# UV_exposure_led_v1_0.net
KiCad netlist of a schematic drawn in EAGLE
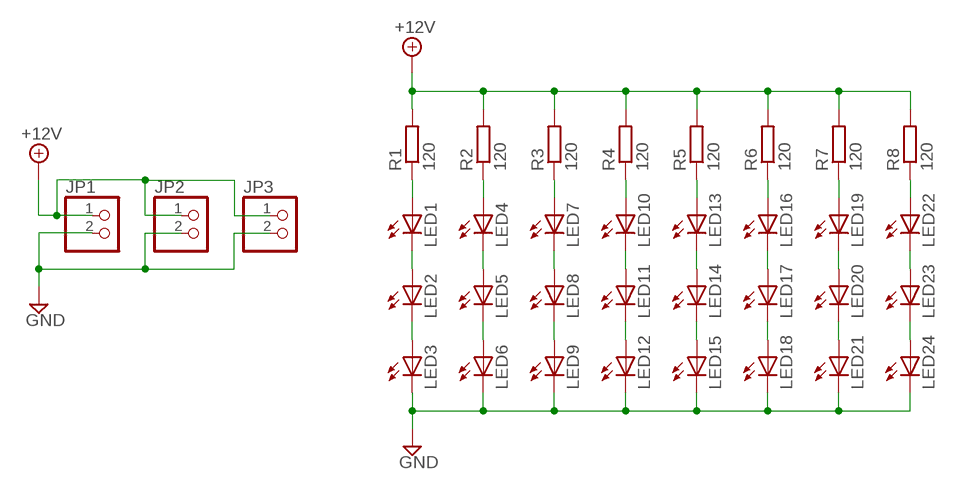
[diagram p0: schematic, sheet 1]

(export (version "E")
  (design (tool "Eeschema 10.0.6"))
  (components
    (comp (ref "JP1")
      (value "PINHD-1X2")
      (footprint "eagle-import:1X02")
      (libsource (lib "eagle-import") (part "PINHD-1X2"))
    )
    (comp (ref "JP2")
      (value "PINHD-1X2")
      (footprint "eagle-import:1X02")
      (libsource (lib "eagle-import") (part "PINHD-1X2"))
    )
    (comp (ref "JP3")
      (value "PINHD-1X2")
      (footprint "eagle-import:1X02")
      (libsource (lib "eagle-import") (part "PINHD-1X2"))
    )
    (comp (ref "LED1")
      (value "LED5MM")
      (footprint "eagle-import:LED5MM")
      (libsource (lib "eagle-import") (part "LED5MM"))
    )
    (comp (ref "LED2")
      (value "LED5MM")
      (footprint "eagle-import:LED5MM")
      (libsource (lib "eagle-import") (part "LED5MM"))
    )
    (comp (ref "LED3")
      (value "LED5MM")
      (footprint "eagle-import:LED5MM")
      (libsource (lib "eagle-import") (part "LED5MM"))
    )
    (comp (ref "LED4")
      (value "LED5MM")
      (footprint "eagle-import:LED5MM")
      (libsource (lib "eagle-import") (part "LED5MM"))
    )
    (comp (ref "LED5")
      (value "LED5MM")
      (footprint "eagle-import:LED5MM")
      (libsource (lib "eagle-import") (part "LED5MM"))
    )
    (comp (ref "LED6")
      (value "LED5MM")
      (footprint "eagle-import:LED5MM")
      (libsource (lib "eagle-import") (part "LED5MM"))
    )
    (comp (ref "LED7")
      (value "LED5MM")
      (footprint "eagle-import:LED5MM")
      (libsource (lib "eagle-import") (part "LED5MM"))
    )
    (comp (ref "LED8")
      (value "LED5MM")
      (footprint "eagle-import:LED5MM")
      (libsource (lib "eagle-import") (part "LED5MM"))
    )
    (comp (ref "LED9")
      (value "LED5MM")
      (footprint "eagle-import:LED5MM")
      (libsource (lib "eagle-import") (part "LED5MM"))
    )
    (comp (ref "LED10")
      (value "LED5MM")
      (footprint "eagle-import:LED5MM")
      (libsource (lib "eagle-import") (part "LED5MM"))
    )
    (comp (ref "LED11")
      (value "LED5MM")
      (footprint "eagle-import:LED5MM")
      (libsource (lib "eagle-import") (part "LED5MM"))
    )
    (comp (ref "LED12")
      (value "LED5MM")
      (footprint "eagle-import:LED5MM")
      (libsource (lib "eagle-import") (part "LED5MM"))
    )
    (comp (ref "LED13")
      (value "LED5MM")
      (footprint "eagle-import:LED5MM")
      (libsource (lib "eagle-import") (part "LED5MM"))
    )
    (comp (ref "LED14")
      (value "LED5MM")
      (footprint "eagle-import:LED5MM")
      (libsource (lib "eagle-import") (part "LED5MM"))
    )
    (comp (ref "LED15")
      (value "LED5MM")
      (footprint "eagle-import:LED5MM")
      (libsource (lib "eagle-import") (part "LED5MM"))
    )
    (comp (ref "LED16")
      (value "LED5MM")
      (footprint "eagle-import:LED5MM")
      (libsource (lib "eagle-import") (part "LED5MM"))
    )
    (comp (ref "LED17")
      (value "LED5MM")
      (footprint "eagle-import:LED5MM")
      (libsource (lib "eagle-import") (part "LED5MM"))
    )
    (comp (ref "LED18")
      (value "LED5MM")
      (footprint "eagle-import:LED5MM")
      (libsource (lib "eagle-import") (part "LED5MM"))
    )
    (comp (ref "LED19")
      (value "LED5MM")
      (footprint "eagle-import:LED5MM")
      (libsource (lib "eagle-import") (part "LED5MM"))
    )
    (comp (ref "LED20")
      (value "LED5MM")
      (footprint "eagle-import:LED5MM")
      (libsource (lib "eagle-import") (part "LED5MM"))
    )
    (comp (ref "LED21")
      (value "LED5MM")
      (footprint "eagle-import:LED5MM")
      (libsource (lib "eagle-import") (part "LED5MM"))
    )
    (comp (ref "LED22")
      (value "LED5MM")
      (footprint "eagle-import:LED5MM")
      (libsource (lib "eagle-import") (part "LED5MM"))
    )
    (comp (ref "LED23")
      (value "LED5MM")
      (footprint "eagle-import:LED5MM")
      (libsource (lib "eagle-import") (part "LED5MM"))
    )
    (comp (ref "LED24")
      (value "LED5MM")
      (footprint "eagle-import:LED5MM")
      (libsource (lib "eagle-import") (part "LED5MM"))
    )
    (comp (ref "R1")
      (value "120")
      (footprint "eagle-import:R1206W")
      (libsource (lib "eagle-import") (part "R-EU_R1206W"))
    )
    (comp (ref "R2")
      (value "120")
      (footprint "eagle-import:R1206W")
      (libsource (lib "eagle-import") (part "R-EU_R1206W"))
    )
    (comp (ref "R3")
      (value "120")
      (footprint "eagle-import:R1206W")
      (libsource (lib "eagle-import") (part "R-EU_R1206W"))
    )
    (comp (ref "R4")
      (value "120")
      (footprint "eagle-import:R1206W")
      (libsource (lib "eagle-import") (part "R-EU_R1206W"))
    )
    (comp (ref "R5")
      (value "120")
      (footprint "eagle-import:R1206W")
      (libsource (lib "eagle-import") (part "R-EU_R1206W"))
    )
    (comp (ref "R6")
      (value "120")
      (footprint "eagle-import:R1206W")
      (libsource (lib "eagle-import") (part "R-EU_R1206W"))
    )
    (comp (ref "R7")
      (value "120")
      (footprint "eagle-import:R1206W")
      (libsource (lib "eagle-import") (part "R-EU_R1206W"))
    )
    (comp (ref "R8")
      (value "120")
      (footprint "eagle-import:R1206W")
      (libsource (lib "eagle-import") (part "R-EU_R1206W"))
    )
  )
  (nets
    (net (code "1") (name "+12V") (class "Default")
      (node (ref "JP1") (pin "1") (pinfunction "1_1") (pintype "passive"))
      (node (ref "JP2") (pin "1") (pinfunction "1_1") (pintype "passive"))
      (node (ref "JP3") (pin "1") (pinfunction "1_1") (pintype "passive"))
      (node (ref "R1") (pin "2") (pinfunction "2_2") (pintype "passive"))
      (node (ref "R2") (pin "2") (pinfunction "2_2") (pintype "passive"))
      (node (ref "R3") (pin "2") (pinfunction "2_2") (pintype "passive"))
      (node (ref "R4") (pin "2") (pinfunction "2_2") (pintype "passive"))
      (node (ref "R5") (pin "2") (pinfunction "2_2") (pintype "passive"))
      (node (ref "R6") (pin "2") (pinfunction "2_2") (pintype "passive"))
      (node (ref "R7") (pin "2") (pinfunction "2_2") (pintype "passive"))
      (node (ref "R8") (pin "2") (pinfunction "2_2") (pintype "passive"))
    )
    (net (code "2") (name "GND") (class "Default")
      (node (ref "JP1") (pin "2") (pinfunction "2_2") (pintype "passive"))
      (node (ref "JP2") (pin "2") (pinfunction "2_2") (pintype "passive"))
      (node (ref "JP3") (pin "2") (pinfunction "2_2") (pintype "passive"))
      (node (ref "LED12") (pin "K") (pinfunction "C_K") (pintype "passive"))
      (node (ref "LED15") (pin "K") (pinfunction "C_K") (pintype "passive"))
      (node (ref "LED18") (pin "K") (pinfunction "C_K") (pintype "passive"))
      (node (ref "LED21") (pin "K") (pinfunction "C_K") (pintype "passive"))
      (node (ref "LED24") (pin "K") (pinfunction "C_K") (pintype "passive"))
      (node (ref "LED3") (pin "K") (pinfunction "C_K") (pintype "passive"))
      (node (ref "LED6") (pin "K") (pinfunction "C_K") (pintype "passive"))
      (node (ref "LED9") (pin "K") (pinfunction "C_K") (pintype "passive"))
    )
    (net (code "3") (name "Net-(LED1-C)") (class "Default")
      (node (ref "LED1") (pin "K") (pinfunction "C_K") (pintype "passive"))
      (node (ref "LED2") (pin "A") (pinfunction "A_A") (pintype "passive"))
    )
    (net (code "4") (name "Net-(LED1-PadA)") (class "Default")
      (node (ref "LED1") (pin "A") (pinfunction "A_A") (pintype "passive"))
      (node (ref "R1") (pin "1") (pinfunction "1_1") (pintype "passive"))
    )
    (net (code "5") (name "Net-(LED2-C)") (class "Default")
      (node (ref "LED2") (pin "K") (pinfunction "C_K") (pintype "passive"))
      (node (ref "LED3") (pin "A") (pinfunction "A_A") (pintype "passive"))
    )
    (net (code "6") (name "Net-(LED4-C)") (class "Default")
      (node (ref "LED4") (pin "K") (pinfunction "C_K") (pintype "passive"))
      (node (ref "LED5") (pin "A") (pinfunction "A_A") (pintype "passive"))
    )
    (net (code "7") (name "Net-(LED4-PadA)") (class "Default")
      (node (ref "LED4") (pin "A") (pinfunction "A_A") (pintype "passive"))
      (node (ref "R2") (pin "1") (pinfunction "1_1") (pintype "passive"))
    )
    (net (code "8") (name "Net-(LED5-C)") (class "Default")
      (node (ref "LED5") (pin "K") (pinfunction "C_K") (pintype "passive"))
      (node (ref "LED6") (pin "A") (pinfunction "A_A") (pintype "passive"))
    )
    (net (code "9") (name "Net-(LED7-C)") (class "Default")
      (node (ref "LED7") (pin "K") (pinfunction "C_K") (pintype "passive"))
      (node (ref "LED8") (pin "A") (pinfunction "A_A") (pintype "passive"))
    )
    (net (code "10") (name "Net-(LED7-PadA)") (class "Default")
      (node (ref "LED7") (pin "A") (pinfunction "A_A") (pintype "passive"))
      (node (ref "R3") (pin "1") (pinfunction "1_1") (pintype "passive"))
    )
    (net (code "11") (name "Net-(LED8-C)") (class "Default")
      (node (ref "LED8") (pin "K") (pinfunction "C_K") (pintype "passive"))
      (node (ref "LED9") (pin "A") (pinfunction "A_A") (pintype "passive"))
    )
    (net (code "12") (name "Net-(LED10-C)") (class "Default")
      (node (ref "LED10") (pin "K") (pinfunction "C_K") (pintype "passive"))
      (node (ref "LED11") (pin "A") (pinfunction "A_A") (pintype "passive"))
    )
    (net (code "13") (name "Net-(LED10-PadA)") (class "Default")
      (node (ref "LED10") (pin "A") (pinfunction "A_A") (pintype "passive"))
      (node (ref "R4") (pin "1") (pinfunction "1_1") (pintype "passive"))
    )
    (net (code "14") (name "Net-(LED11-C)") (class "Default")
      (node (ref "LED11") (pin "K") (pinfunction "C_K") (pintype "passive"))
      (node (ref "LED12") (pin "A") (pinfunction "A_A") (pintype "passive"))
    )
    (net (code "15") (name "Net-(LED13-C)") (class "Default")
      (node (ref "LED13") (pin "K") (pinfunction "C_K") (pintype "passive"))
      (node (ref "LED14") (pin "A") (pinfunction "A_A") (pintype "passive"))
    )
    (net (code "16") (name "Net-(LED13-PadA)") (class "Default")
      (node (ref "LED13") (pin "A") (pinfunction "A_A") (pintype "passive"))
      (node (ref "R5") (pin "1") (pinfunction "1_1") (pintype "passive"))
    )
    (net (code "17") (name "Net-(LED14-C)") (class "Default")
      (node (ref "LED14") (pin "K") (pinfunction "C_K") (pintype "passive"))
      (node (ref "LED15") (pin "A") (pinfunction "A_A") (pintype "passive"))
    )
    (net (code "18") (name "Net-(LED16-C)") (class "Default")
      (node (ref "LED16") (pin "K") (pinfunction "C_K") (pintype "passive"))
      (node (ref "LED17") (pin "A") (pinfunction "A_A") (pintype "passive"))
    )
    (net (code "19") (name "Net-(LED16-PadA)") (class "Default")
      (node (ref "LED16") (pin "A") (pinfunction "A_A") (pintype "passive"))
      (node (ref "R6") (pin "1") (pinfunction "1_1") (pintype "passive"))
    )
    (net (code "20") (name "Net-(LED17-C)") (class "Default")
      (node (ref "LED17") (pin "K") (pinfunction "C_K") (pintype "passive"))
      (node (ref "LED18") (pin "A") (pinfunction "A_A") (pintype "passive"))
    )
    (net (code "21") (name "Net-(LED19-C)") (class "Default")
      (node (ref "LED19") (pin "K") (pinfunction "C_K") (pintype "passive"))
      (node (ref "LED20") (pin "A") (pinfunction "A_A") (pintype "passive"))
    )
    (net (code "22") (name "Net-(LED19-PadA)") (class "Default")
      (node (ref "LED19") (pin "A") (pinfunction "A_A") (pintype "passive"))
      (node (ref "R7") (pin "1") (pinfunction "1_1") (pintype "passive"))
    )
    (net (code "23") (name "Net-(LED20-C)") (class "Default")
      (node (ref "LED20") (pin "K") (pinfunction "C_K") (pintype "passive"))
      (node (ref "LED21") (pin "A") (pinfunction "A_A") (pintype "passive"))
    )
    (net (code "24") (name "Net-(LED22-C)") (class "Default")
      (node (ref "LED22") (pin "K") (pinfunction "C_K") (pintype "passive"))
      (node (ref "LED23") (pin "A") (pinfunction "A_A") (pintype "passive"))
    )
    (net (code "25") (name "Net-(LED22-PadA)") (class "Default")
      (node (ref "LED22") (pin "A") (pinfunction "A_A") (pintype "passive"))
      (node (ref "R8") (pin "1") (pinfunction "1_1") (pintype "passive"))
    )
    (net (code "26") (name "Net-(LED23-C)") (class "Default")
      (node (ref "LED23") (pin "K") (pinfunction "C_K") (pintype "passive"))
      (node (ref "LED24") (pin "A") (pinfunction "A_A") (pintype "passive"))
    )
  )
)
